# ISO7240F.net
KiCad netlist of a schematic drawn in Altium Designer
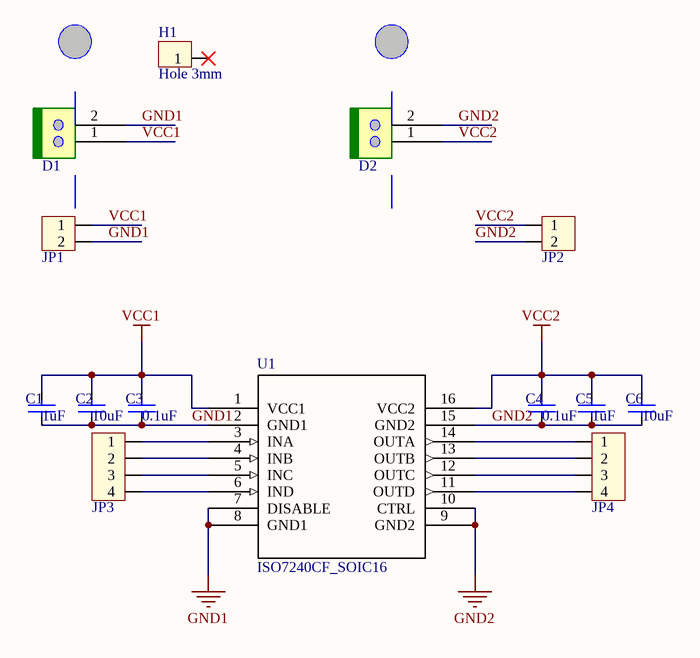
[diagram p0: ISO7240F.SchDoc]

(export (version "E")
  (design (tool "Eeschema 10.0.6"))
  (components
    (comp (ref "C1")
      (value "1uF")
      (footprint "0805_C")
      (description "0805 SMD capacitor")
      (libsource (lib "Thach") (part "0805_C"))
    )
    (comp (ref "C2")
      (value "10uF")
      (footprint "0805_C")
      (description "0805 SMD capacitor")
      (libsource (lib "Thach") (part "0805_C"))
    )
    (comp (ref "C3")
      (value "0.1uF")
      (footprint "0805_C")
      (description "0805 SMD capacitor")
      (libsource (lib "Thach") (part "0805_C"))
    )
    (comp (ref "C4")
      (value "0.1uF")
      (footprint "0805_C")
      (description "0805 SMD capacitor")
      (libsource (lib "Thach") (part "0805_C"))
    )
    (comp (ref "C5")
      (value "1uF")
      (footprint "0805_C")
      (description "0805 SMD capacitor")
      (libsource (lib "Thach") (part "0805_C"))
    )
    (comp (ref "C6")
      (value "10uF")
      (footprint "0805_C")
      (description "0805 SMD capacitor")
      (libsource (lib "Thach") (part "0805_C"))
    )
    (comp (ref "D1") (value "DOMINO") (footprint "DOMINO2") (libsource (lib "Thach") (part "Domino2_5mm")))
    (comp (ref "D2") (value "DOMINO") (footprint "DOMINO2") (libsource (lib "Thach") (part "Domino2_5mm")))
    (comp (ref "H1") (value "Hole 3mm") (footprint "Hole_3mm") (libsource (lib "Thach") (part "Hole_3mm")))
    (comp (ref "JP1")
      (value "JP2")
      (footprint "HEAD2")
      (description "Connector 2")
      (libsource (lib "") (part "HEAD2_1"))
    )
    (comp (ref "JP2")
      (value "JP2")
      (footprint "HEAD2")
      (description "Connector 2")
      (libsource (lib "Thach") (part "HEAD2"))
    )
    (comp (ref "JP3")
      (value "JP4")
      (footprint "HEAD4")
      (description "Connector 4")
      (libsource (lib "Thach") (part "HEAD4"))
    )
    (comp (ref "JP4")
      (value "JP4")
      (footprint "HEAD4")
      (description "Connector 4")
      (libsource (lib "") (part "HEAD4_1"))
    )
    (comp (ref "U1")
      (value "ISO7240CF_SOIC16")
      (footprint "DW16_ISO7240CF")
      (libsource (lib "Thach") (part "ISO7240CF_SOIC16"))
    )
  )
  (nets
    (net (code "1") (name "GND1") (class "Default")
      (node (ref "C1") (pin "1") (pinfunction "1_1") (pintype "passive"))
      (node (ref "C2") (pin "1") (pinfunction "1_1") (pintype "passive"))
      (node (ref "C3") (pin "1") (pinfunction "1_1") (pintype "passive"))
      (node (ref "D1") (pin "2") (pintype "passive"))
      (node (ref "JP1") (pin "2") (pinfunction "2_2") (pintype "passive"))
      (node (ref "U1") (pin "2") (pinfunction "GND1_2") (pintype "power_in"))
      (node (ref "U1") (pin "7") (pinfunction "DISABLE_7") (pintype "passive"))
      (node (ref "U1") (pin "8") (pinfunction "GND1_8") (pintype "power_in"))
    )
    (net (code "2") (name "GND2") (class "Default")
      (node (ref "C4") (pin "1") (pinfunction "1_1") (pintype "passive"))
      (node (ref "C5") (pin "1") (pinfunction "1_1") (pintype "passive"))
      (node (ref "C6") (pin "1") (pinfunction "1_1") (pintype "passive"))
      (node (ref "D2") (pin "2") (pintype "passive"))
      (node (ref "JP2") (pin "2") (pinfunction "2_2") (pintype "passive"))
      (node (ref "U1") (pin "10") (pinfunction "CTRL_10") (pintype "passive"))
      (node (ref "U1") (pin "15") (pinfunction "GND2_15") (pintype "power_in"))
      (node (ref "U1") (pin "9") (pinfunction "GND2_9") (pintype "power_in"))
    )
    (net (code "3") (name "Net-(U1-INA)") (class "Default")
      (node (ref "JP3") (pin "1") (pinfunction "1_1") (pintype "passive"))
      (node (ref "U1") (pin "3") (pinfunction "INA_3") (pintype "input"))
    )
    (net (code "4") (name "Net-(U1-INB)") (class "Default")
      (node (ref "JP3") (pin "2") (pinfunction "2_2") (pintype "passive"))
      (node (ref "U1") (pin "4") (pinfunction "INB_4") (pintype "input"))
    )
    (net (code "5") (name "Net-(U1-INC)") (class "Default")
      (node (ref "JP3") (pin "3") (pinfunction "3_3") (pintype "passive"))
      (node (ref "U1") (pin "5") (pinfunction "INC_5") (pintype "input"))
    )
    (net (code "6") (name "Net-(U1-IND)") (class "Default")
      (node (ref "JP3") (pin "4") (pinfunction "4_4") (pintype "passive"))
      (node (ref "U1") (pin "6") (pinfunction "IND_6") (pintype "input"))
    )
    (net (code "7") (name "Net-(U1-OUTA)") (class "Default")
      (node (ref "JP4") (pin "1") (pinfunction "1_1") (pintype "passive"))
      (node (ref "U1") (pin "14") (pinfunction "OUTA_14") (pintype "output"))
    )
    (net (code "8") (name "Net-(U1-OUTB)") (class "Default")
      (node (ref "JP4") (pin "2") (pinfunction "2_2") (pintype "passive"))
      (node (ref "U1") (pin "13") (pinfunction "OUTB_13") (pintype "output"))
    )
    (net (code "9") (name "Net-(U1-OUTC)") (class "Default")
      (node (ref "JP4") (pin "3") (pinfunction "3_3") (pintype "passive"))
      (node (ref "U1") (pin "12") (pinfunction "OUTC_12") (pintype "output"))
    )
    (net (code "10") (name "Net-(U1-OUTD)") (class "Default")
      (node (ref "JP4") (pin "4") (pinfunction "4_4") (pintype "passive"))
      (node (ref "U1") (pin "11") (pinfunction "OUTD_11") (pintype "output"))
    )
    (net (code "11") (name "VCC1") (class "Default")
      (node (ref "C1") (pin "2") (pinfunction "2_2") (pintype "passive"))
      (node (ref "C2") (pin "2") (pinfunction "2_2") (pintype "passive"))
      (node (ref "C3") (pin "2") (pinfunction "2_2") (pintype "passive"))
      (node (ref "D1") (pin "1") (pintype "passive"))
      (node (ref "JP1") (pin "1") (pinfunction "1_1") (pintype "passive"))
      (node (ref "U1") (pin "1") (pinfunction "VCC1_1") (pintype "power_in"))
    )
    (net (code "12") (name "VCC2") (class "Default")
      (node (ref "C4") (pin "2") (pinfunction "2_2") (pintype "passive"))
      (node (ref "C5") (pin "2") (pinfunction "2_2") (pintype "passive"))
      (node (ref "C6") (pin "2") (pinfunction "2_2") (pintype "passive"))
      (node (ref "D2") (pin "1") (pintype "passive"))
      (node (ref "JP2") (pin "1") (pinfunction "1_1") (pintype "passive"))
      (node (ref "U1") (pin "16") (pinfunction "VCC2_16") (pintype "power_in"))
    )
    (net (code "13") (name "unconnected-(H1-Pad1)") (class "Default")
      (node (ref "H1") (pin "1") (pinfunction "1_1") (pintype "passive+no_connect"))
    )
  )
)
